# DC.net
KiCad netlist of a schematic drawn in EasyEDA Pro
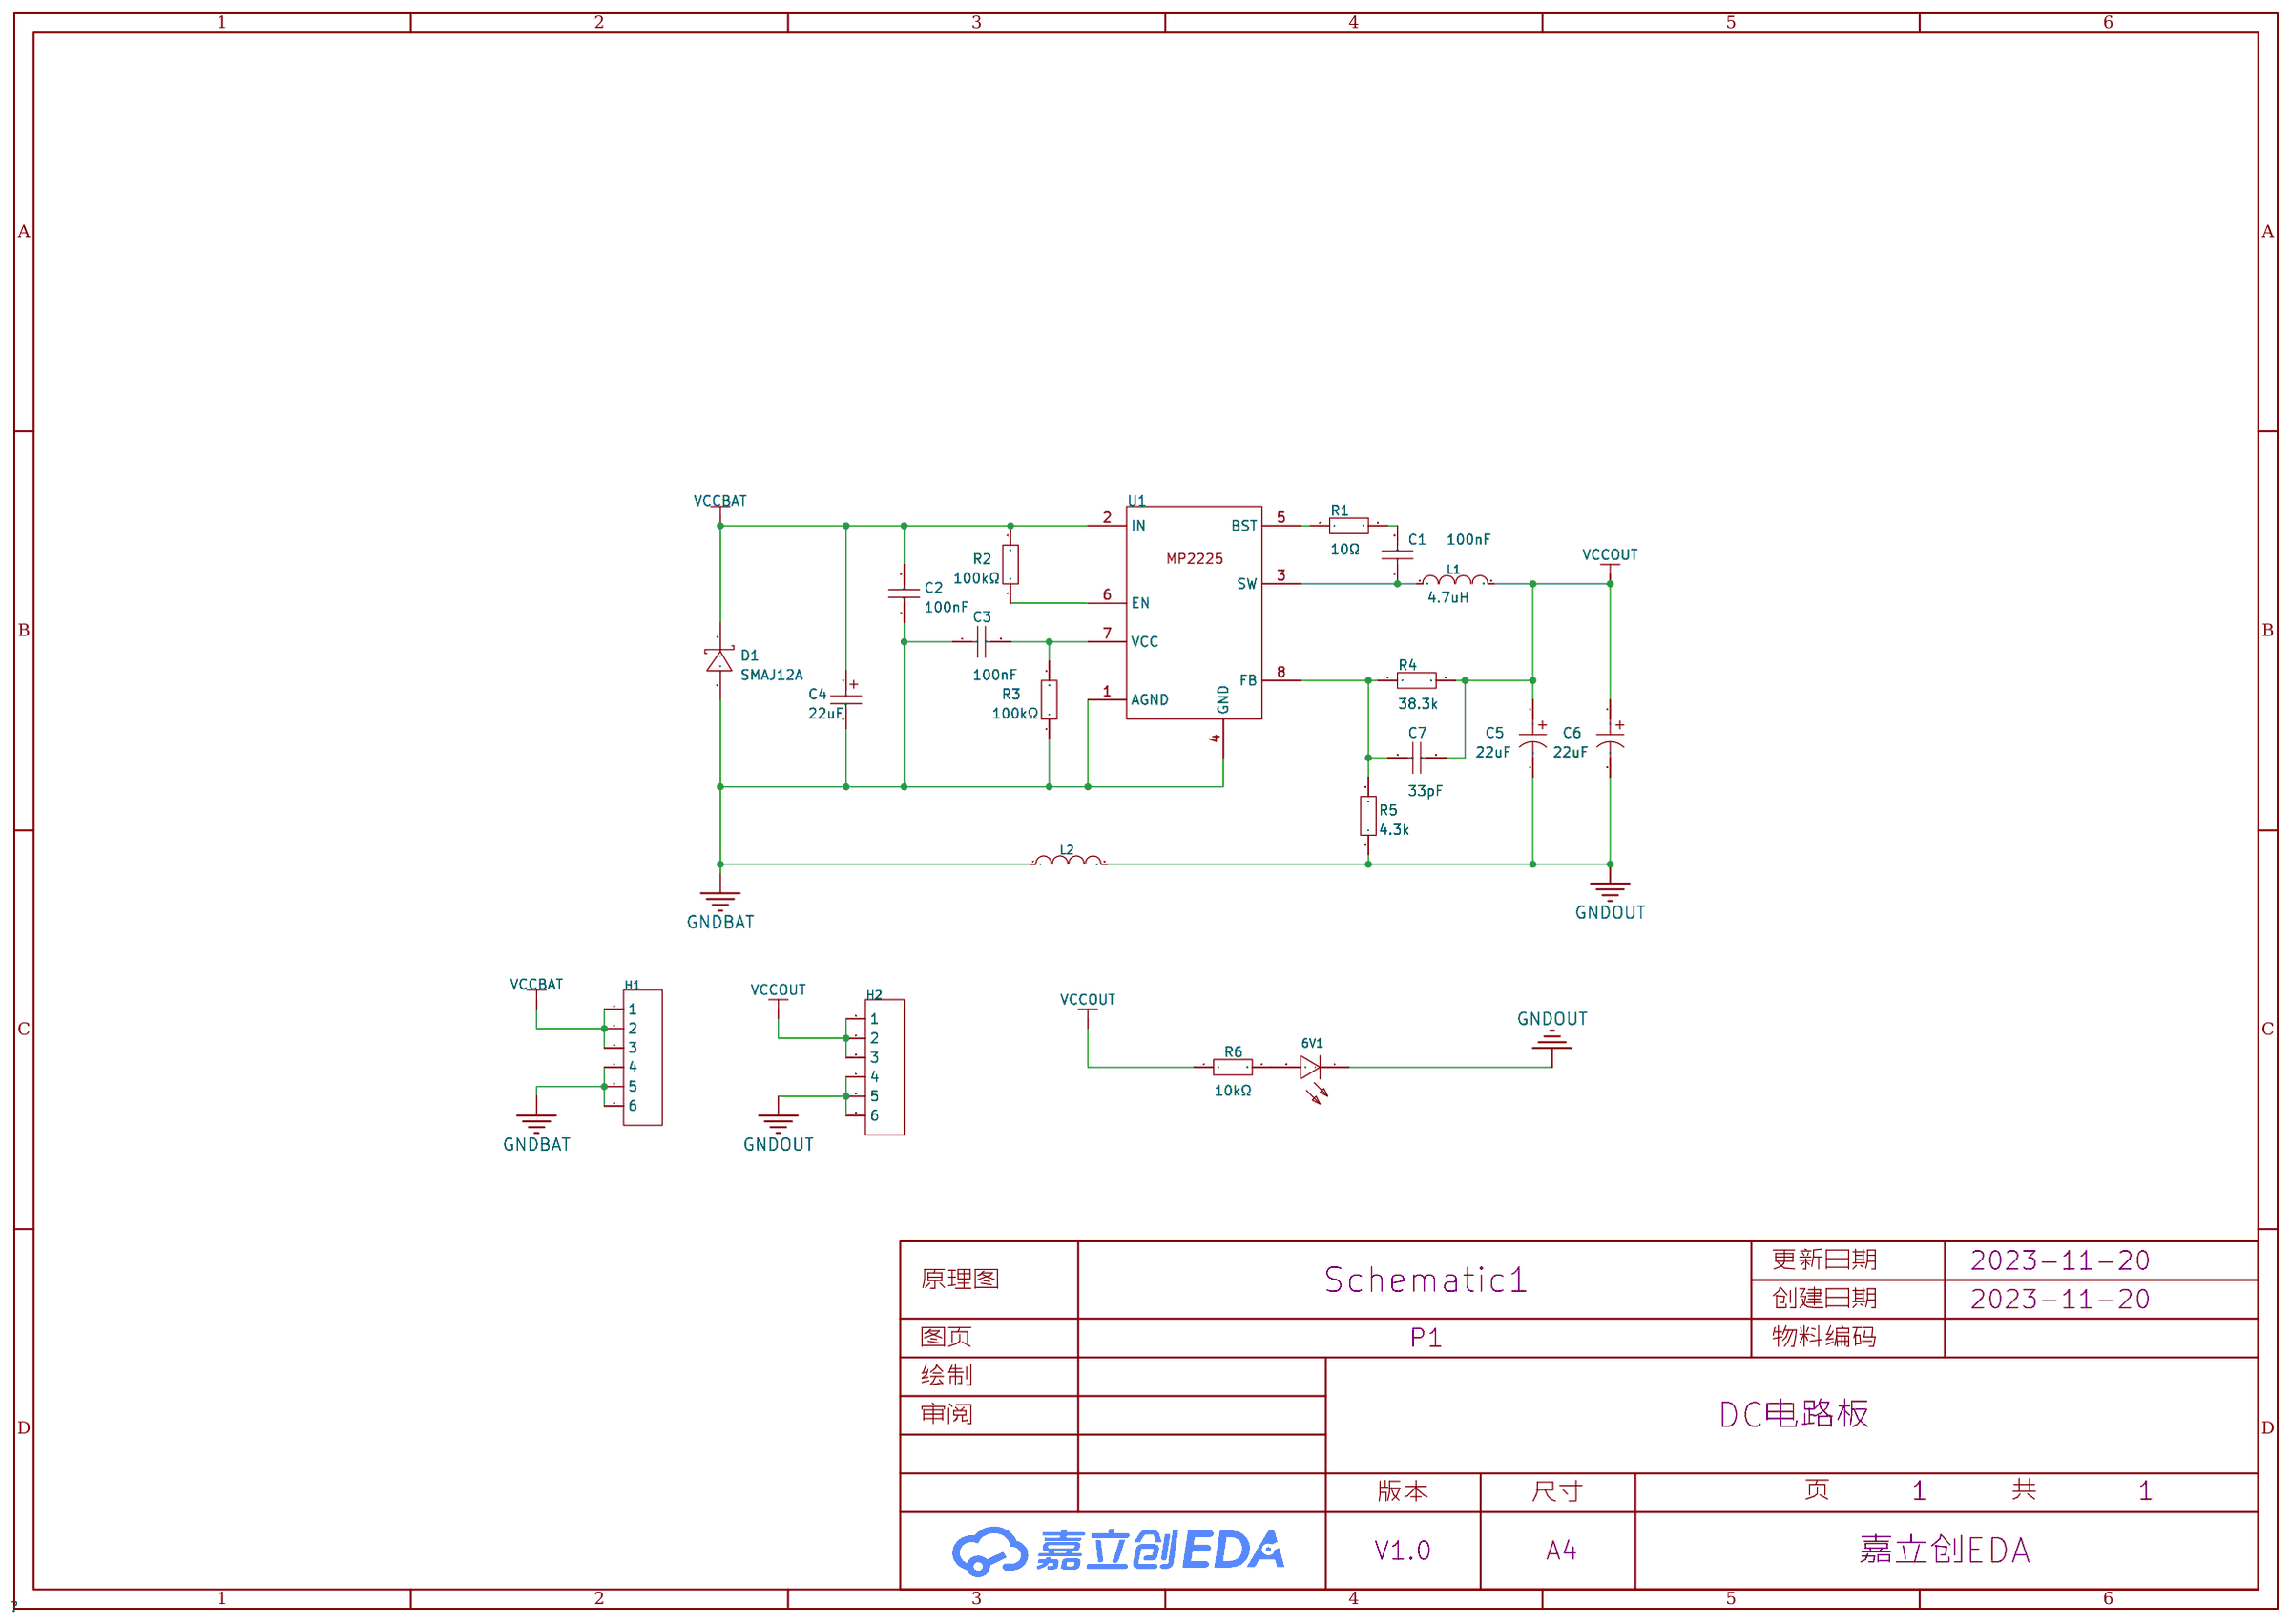
[diagram p0: schematic sheet]

(export (version "E")
  (design (tool "Eeschema 10.0.6"))
  (components
    (comp (ref "6V1")
      (value "NCD0603W1")
      (footprint "easyedapro:LED0603-RD")
      (description "发光颜色:白灯;")
      (fields (field (name "Manufacturer") "国星光电"))
      (libsource (lib "easyedapro") (part "FC-D1608WD-460H5"))
    )
    (comp (ref "C1")
      (value "100nF")
      (footprint "easyedapro:C0603")
      (description "容值:100nF;精度:±10%;额定电压:50V;材质(温度系数):X7R;")
      (fields (field (name "Manufacturer Part") "0603B104K500NT") (field (name "Manufacturer") "FH(风华)"))
      (libsource (lib "easyedapro") (part "0603B104K500NT"))
    )
    (comp (ref "C2")
      (value "100nF")
      (footprint "easyedapro:C0603")
      (description "容值:100nF;精度:±10%;额定电压:50V;材质(温度系数):X7R;")
      (fields (field (name "Manufacturer Part") "0603B104K500NT") (field (name "Manufacturer") "FH(风华)"))
      (libsource (lib "easyedapro") (part "0603B104K500NT"))
    )
    (comp (ref "C3")
      (value "100nF")
      (footprint "easyedapro:C0603")
      (description "容值:100nF;精度:±10%;额定电压:50V;材质(温度系数):X7R;")
      (fields (field (name "Manufacturer Part") "0603B104K500NT") (field (name "Manufacturer") "FH(风华)"))
      (libsource (lib "easyedapro") (part "0603B104K500NT"))
    )
    (comp (ref "C4")
      (value "22uF")
      (footprint "easyedapro:CAP-SMD_L6.0-W3.2-R-RD")
      (description "容值:22uF;精度:±10%;额定电压:25V;等效串联电阻:1.4Ω@100kHz;")
      (fields (field (name "Manufacturer Part") "TAJC226K025RNJ") (field (name "Manufacturer") "Kyocera AVX"))
      (libsource (lib "easyedapro") (part "TAJC226K025RNJ"))
    )
    (comp (ref "C5")
      (value "22uF")
      (footprint "easyedapro:CAP-SMD_L3.2-W1.6")
      (description "容值:22uF;精度:±10%;额定电压:16V;等效串联电阻:6Ω@100kHz;")
      (fields
        (field (name "Manufacturer Part") "CA45-A-16V-22uF-K")
        (field (name "Manufacturer") "CEC(振华新云)")
      )
      (libsource (lib "easyedapro") (part "CA45-A-16V-22UF-K"))
    )
    (comp (ref "C6")
      (value "22uF")
      (footprint "easyedapro:CAP-SMD_L3.2-W1.6")
      (description "容值:22uF;精度:±10%;额定电压:16V;等效串联电阻:6Ω@100kHz;")
      (fields
        (field (name "Manufacturer Part") "CA45-A-16V-22uF-K")
        (field (name "Manufacturer") "CEC(振华新云)")
      )
      (libsource (lib "easyedapro") (part "CA45-A-16V-22UF-K"))
    )
    (comp (ref "C7")
      (value "33pF")
      (footprint "easyedapro:C0603")
      (description "容值:33pF;精度:±5%;额定电压:50V;材质(温度系数):C0G;")
      (fields
        (field (name "Manufacturer Part") "CL10C330JB8NNNC")
        (field (name "Manufacturer") "SAMSUNG(三星)")
      )
      (libsource (lib "easyedapro") (part "CL10C330JB8NNNC"))
    )
    (comp (ref "D1")
      (value "SMAJ12A")
      (footprint "easyedapro:SMA_L4.4-W2.7-LS5.1-RD")
      (description "极性:单向;反向截止电压(Vrwm):12V;击穿电压:13.3V;峰值脉冲电流(Ipp)@10/1000μs:20.1A;最大钳位电压:19.9V;")
      (fields (field (name "Manufacturer") "BORN(伯恩半导体)"))
      (libsource (lib "easyedapro") (part "SMAJ12A_C152123"))
    )
    (comp (ref "H1")
      (value "~")
      (footprint "easyedapro:HDR-TH_6P-P2.54-V-M-1")
      (libsource (lib "easyedapro") (part "Header-Male-2.54_1x6"))
    )
    (comp (ref "H2")
      (value "~")
      (footprint "easyedapro:HDR-TH_6P-P2.54-V-M-1")
      (libsource (lib "easyedapro") (part "Header-Male-2.54_1x6"))
    )
    (comp (ref "L1")
      (value "4.7uH")
      (footprint "easyedapro:IND-SMD_L5.4-W5.2_FXL0530")
      (description "电感值:4.7uH;精度:±20%;额定电流:4.5A;饱和电流(Isat):5A;")
      (fields (field (name "Manufacturer Part") "FXL0530-4R7-M") (field (name "Manufacturer") "cjiang(长江微电)"))
      (libsource (lib "easyedapro") (part "FXL0530-4R7-M"))
    )
    (comp (ref "L2")
      (value "CBG201209U000T")
      (footprint "easyedapro:L0805")
      (description "标称阻抗@测试频率:0Ω@100MHz;直流电阻(RDC):80mΩ;")
      (fields (field (name "Manufacturer") "FH(风华)"))
      (libsource (lib "easyedapro") (part "CBG201209U000T"))
    )
    (comp (ref "R1")
      (value "10Ω")
      (footprint "easyedapro:R0603")
      (description "电阻类型:厚膜电阻;阻值:10Ω;精度:±1%;功率:100mW;")
      (fields
        (field (name "Manufacturer Part") "0603WAF100JT5E")
        (field (name "Manufacturer") "UNI-ROYAL(厚声)")
      )
      (libsource (lib "easyedapro") (part "0603WAF100JT5E"))
    )
    (comp (ref "R2")
      (value "100kΩ")
      (footprint "easyedapro:R0603")
      (description "电阻类型:厚膜电阻;阻值:100kΩ;精度:±1%;功率:100mW;")
      (fields (field (name "Manufacturer Part") "RC0603FR-07100KL") (field (name "Manufacturer") "YAGEO(国巨)"))
      (libsource (lib "easyedapro") (part "RC0603FR-07100KL"))
    )
    (comp (ref "R3")
      (value "100kΩ")
      (footprint "easyedapro:R0603")
      (description "电阻类型:厚膜电阻;阻值:100kΩ;精度:±1%;功率:100mW;")
      (fields (field (name "Manufacturer Part") "RC0603FR-07100KL") (field (name "Manufacturer") "YAGEO(国巨)"))
      (libsource (lib "easyedapro") (part "RC0603FR-07100KL"))
    )
    (comp (ref "R4")
      (value "38.3k")
      (footprint "easyedapro:R0603")
      (description "电阻类型:厚膜电阻;阻值:40.2kΩ;精度:±1%;功率:100mW;")
      (fields
        (field (name "Manufacturer Part") "0603WAF4022T5E")
        (field (name "Manufacturer") "UNI-ROYAL(厚声)")
      )
      (libsource (lib "easyedapro") (part "0603WAF4022T5E"))
    )
    (comp (ref "R5")
      (value "4.3k")
      (footprint "easyedapro:R0603")
      (description "电阻类型:厚膜电阻;阻值:5.49kΩ;精度:±1%;功率:100mW;")
      (fields
        (field (name "Manufacturer Part") "0603WAF5491T5E")
        (field (name "Manufacturer") "UNI-ROYAL(厚声)")
      )
      (libsource (lib "easyedapro") (part "0603WAF5491T5E"))
    )
    (comp (ref "R6")
      (value "10kΩ")
      (footprint "easyedapro:R0603")
      (description "电阻类型:厚膜电阻;阻值:10kΩ;精度:±1%;功率:100mW;")
      (fields
        (field (name "Manufacturer Part") "0603WAF1002T5E")
        (field (name "Manufacturer") "UNI-ROYAL(厚声)")
      )
      (libsource (lib "easyedapro") (part "0603WAF1002T5E"))
    )
    (comp (ref "U1") (value "~") (description "DC-DC芯片") (libsource (lib "easyedapro") (part "MP2225")))
  )
  (nets
    (net (code "1") (name "GNDBAT") (class "Default")
      (node (ref "C2") (pin "1") (pinfunction "1_1") (pintype "input"))
      (node (ref "C3") (pin "2") (pinfunction "2_2") (pintype "input"))
      (node (ref "C4") (pin "2") (pinfunction "2_2") (pintype "input"))
      (node (ref "D1") (pin "2") (pinfunction "A_2") (pintype "input"))
      (node (ref "H1") (pin "4") (pinfunction "4_4") (pintype "input"))
      (node (ref "H1") (pin "5") (pinfunction "5_5") (pintype "input"))
      (node (ref "H1") (pin "6") (pinfunction "6_6") (pintype "input"))
      (node (ref "L2") (pin "1") (pinfunction "1_1") (pintype "input"))
      (node (ref "R3") (pin "1") (pinfunction "1_1") (pintype "input"))
      (node (ref "U1") (pin "1") (pinfunction "AGND_1") (pintype "input"))
      (node (ref "U1") (pin "4") (pinfunction "GND_4") (pintype "input"))
    )
    (net (code "2") (name "GNDOUT") (class "Default")
      (node (ref "6V1") (pin "1") (pinfunction "-_1") (pintype "input"))
      (node (ref "C5") (pin "2") (pinfunction "2_2") (pintype "input"))
      (node (ref "C6") (pin "2") (pinfunction "2_2") (pintype "input"))
      (node (ref "H2") (pin "4") (pinfunction "4_4") (pintype "input"))
      (node (ref "H2") (pin "5") (pinfunction "5_5") (pintype "input"))
      (node (ref "H2") (pin "6") (pinfunction "6_6") (pintype "input"))
      (node (ref "L2") (pin "2") (pinfunction "2_2") (pintype "input"))
      (node (ref "R5") (pin "1") (pinfunction "1_1") (pintype "input"))
    )
    (net (code "3") (name "Net-(6V1-+)") (class "Default")
      (node (ref "6V1") (pin "2") (pinfunction "+_2") (pintype "input"))
      (node (ref "R6") (pin "2") (pinfunction "2_2") (pintype "input"))
    )
    (net (code "4") (name "Net-(C1-Pad2)") (class "Default")
      (node (ref "C1") (pin "2") (pinfunction "2_2") (pintype "input"))
      (node (ref "R1") (pin "2") (pinfunction "2_2") (pintype "input"))
    )
    (net (code "5") (name "Net-(U1-BST)") (class "Default")
      (node (ref "R1") (pin "1") (pinfunction "1_1") (pintype "input"))
      (node (ref "U1") (pin "5") (pinfunction "BST_5") (pintype "input"))
    )
    (net (code "6") (name "Net-(U1-EN)") (class "Default")
      (node (ref "R2") (pin "1") (pinfunction "1_1") (pintype "input"))
      (node (ref "U1") (pin "6") (pinfunction "EN_6") (pintype "input"))
    )
    (net (code "7") (name "Net-(U1-FB)") (class "Default")
      (node (ref "C7") (pin "2") (pinfunction "2_2") (pintype "input"))
      (node (ref "R4") (pin "2") (pinfunction "2_2") (pintype "input"))
      (node (ref "R5") (pin "2") (pinfunction "2_2") (pintype "input"))
      (node (ref "U1") (pin "8") (pinfunction "FB_8") (pintype "input"))
    )
    (net (code "8") (name "Net-(U1-SW)") (class "Default")
      (node (ref "C1") (pin "1") (pinfunction "1_1") (pintype "input"))
      (node (ref "L1") (pin "1") (pinfunction "1_1") (pintype "input"))
      (node (ref "U1") (pin "3") (pinfunction "SW_3") (pintype "input"))
    )
    (net (code "9") (name "Net-(U1-VCC)") (class "Default")
      (node (ref "C3") (pin "1") (pinfunction "1_1") (pintype "input"))
      (node (ref "R3") (pin "2") (pinfunction "2_2") (pintype "input"))
      (node (ref "U1") (pin "7") (pinfunction "VCC_7") (pintype "input"))
    )
    (net (code "10") (name "VCCBAT") (class "Default")
      (node (ref "C2") (pin "2") (pinfunction "2_2") (pintype "input"))
      (node (ref "C4") (pin "1") (pinfunction "1_1") (pintype "input"))
      (node (ref "D1") (pin "1") (pinfunction "K_1") (pintype "input"))
      (node (ref "H1") (pin "1") (pinfunction "1_1") (pintype "input"))
      (node (ref "H1") (pin "2") (pinfunction "2_2") (pintype "input"))
      (node (ref "H1") (pin "3") (pinfunction "3_3") (pintype "input"))
      (node (ref "R2") (pin "2") (pinfunction "2_2") (pintype "input"))
      (node (ref "U1") (pin "2") (pinfunction "IN_2") (pintype "input"))
    )
    (net (code "11") (name "VCCOUT") (class "Default")
      (node (ref "C5") (pin "1") (pinfunction "1_1") (pintype "input"))
      (node (ref "C6") (pin "1") (pinfunction "1_1") (pintype "input"))
      (node (ref "C7") (pin "1") (pinfunction "1_1") (pintype "input"))
      (node (ref "H2") (pin "1") (pinfunction "1_1") (pintype "input"))
      (node (ref "H2") (pin "2") (pinfunction "2_2") (pintype "input"))
      (node (ref "H2") (pin "3") (pinfunction "3_3") (pintype "input"))
      (node (ref "L1") (pin "2") (pinfunction "2_2") (pintype "input"))
      (node (ref "R4") (pin "1") (pinfunction "1_1") (pintype "input"))
      (node (ref "R6") (pin "1") (pinfunction "1_1") (pintype "input"))
    )
  )
)
